# EasyEDA.net
KiCad netlist of a schematic drawn in EasyEDA Pro
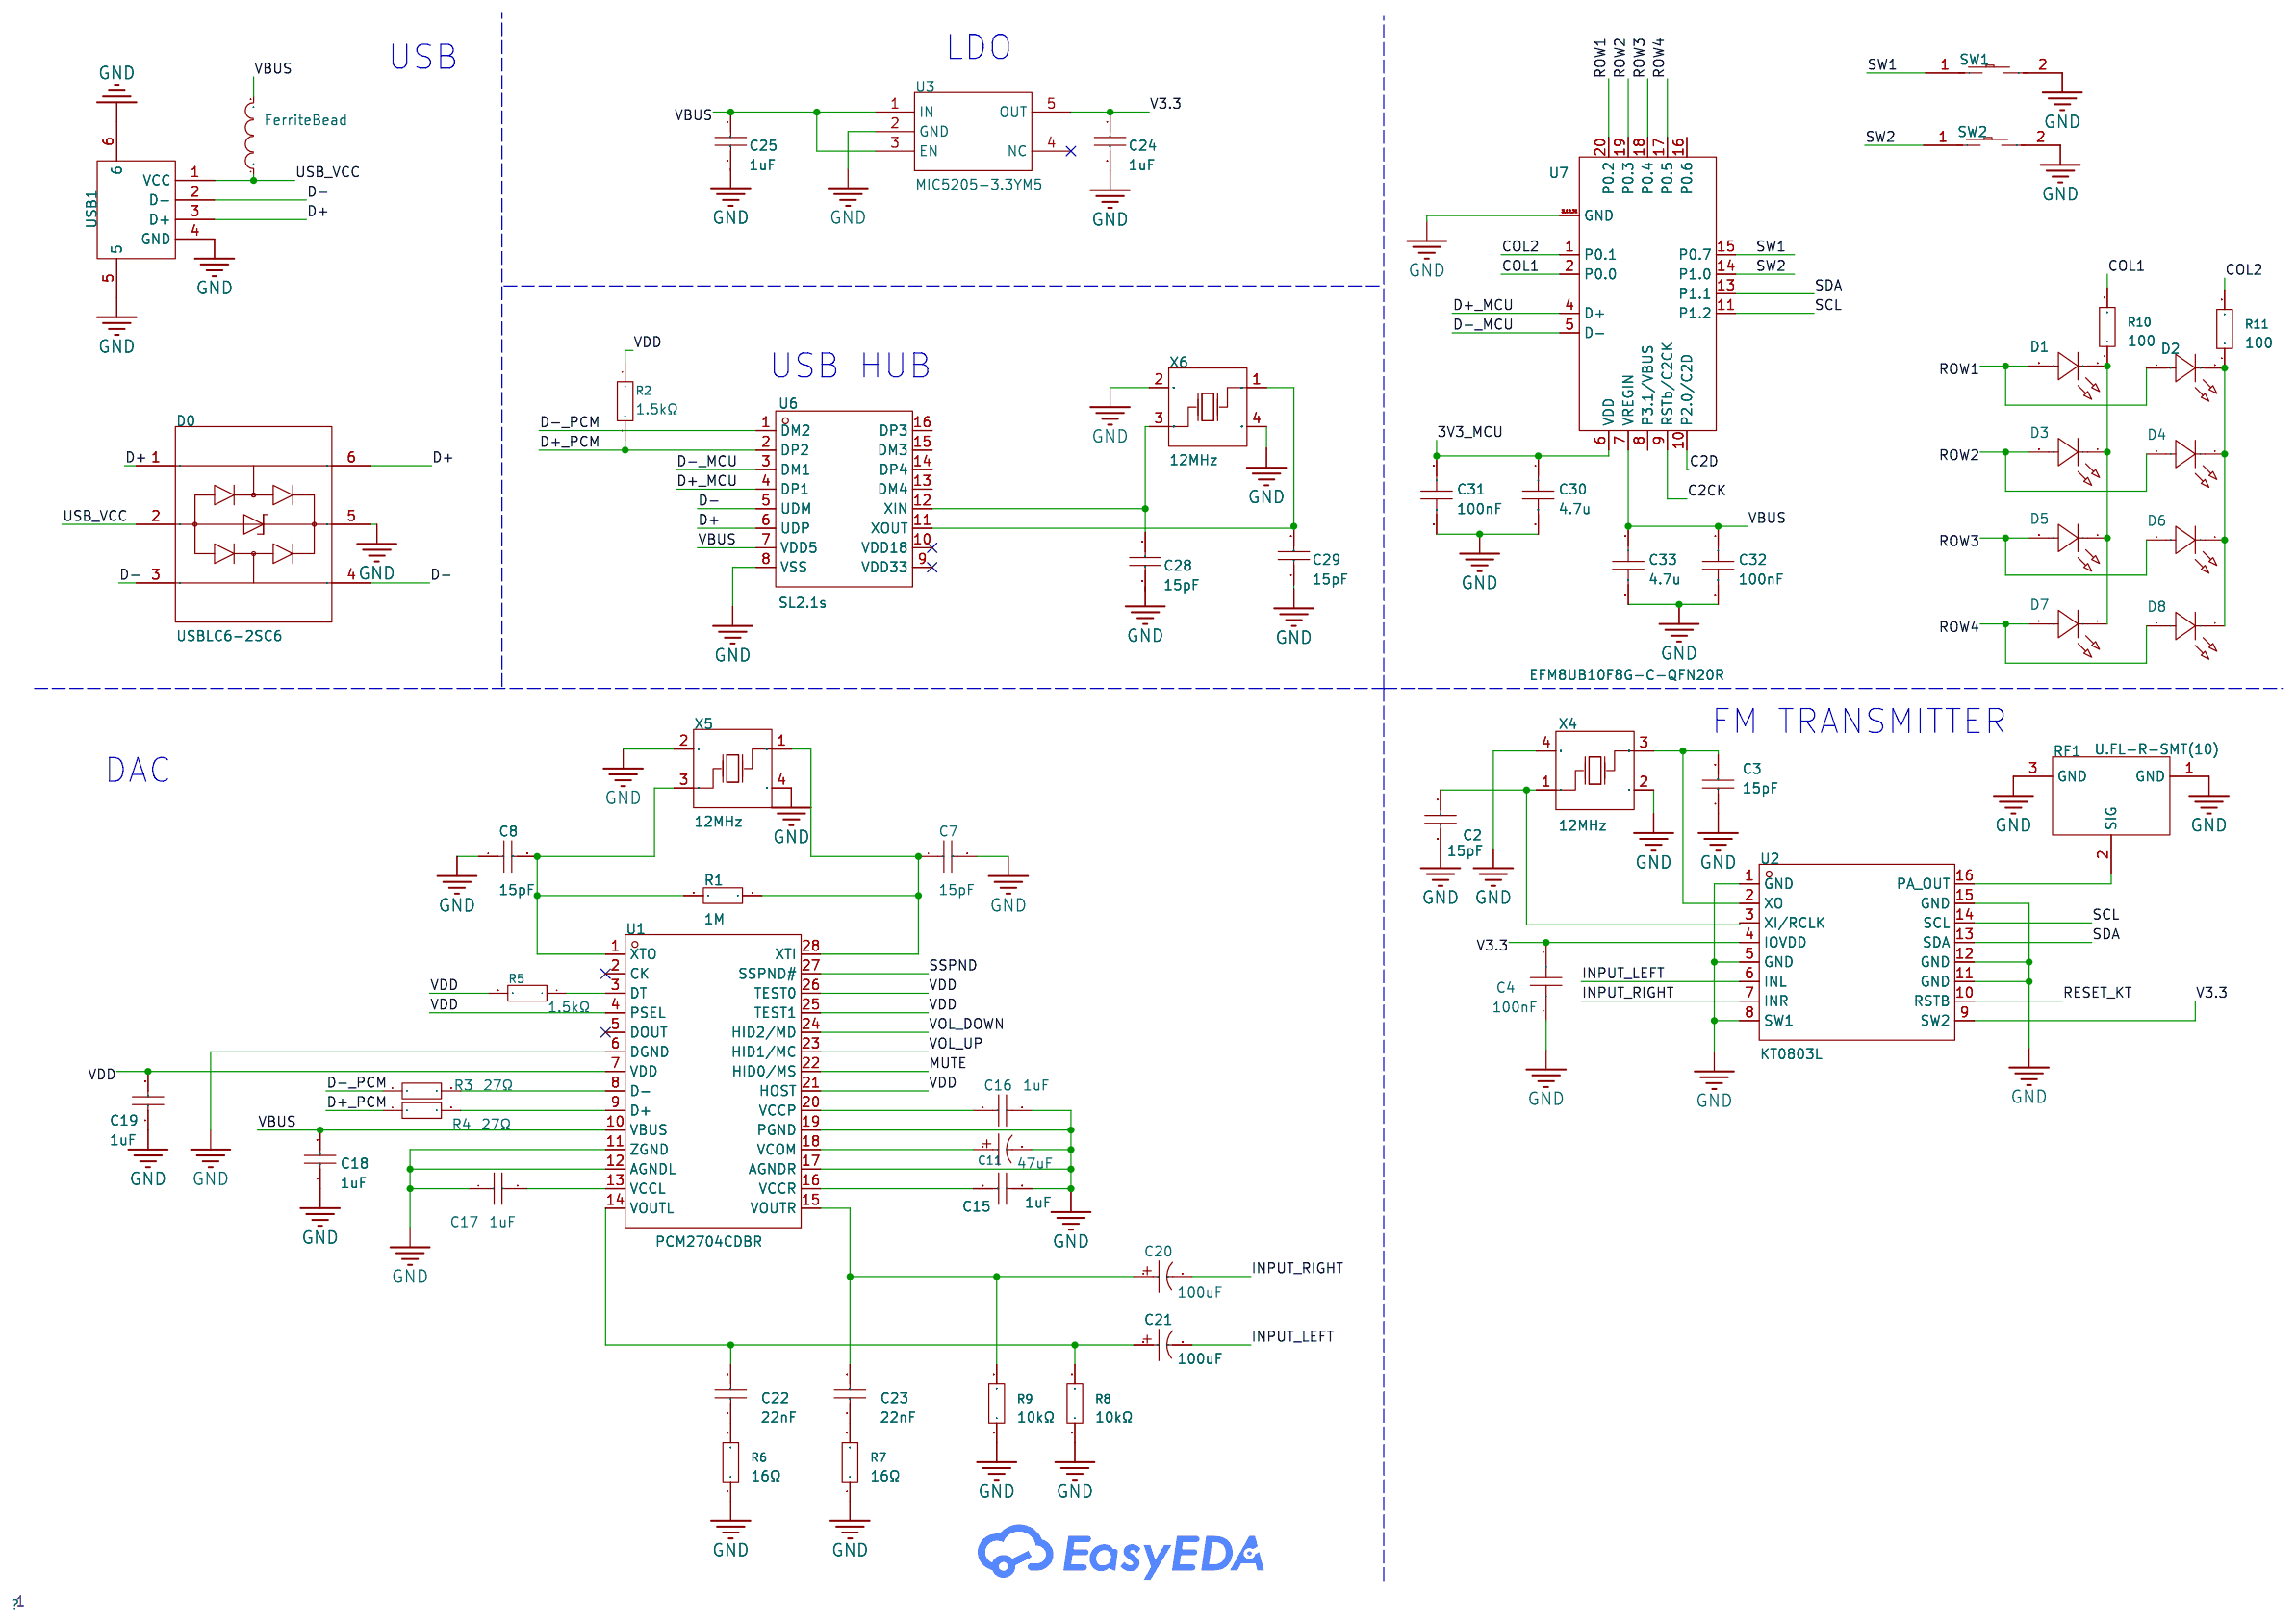
[diagram p0: schematic sheet]

(export (version "E")
  (design (tool "Eeschema 10.0.6"))
  (components
    (comp (ref "C2")
      (value "15pF")
      (footprint "easyedapro:C0402")
      (fields (field (name "Manufacturer Part") "0402CG150J500NT") (field (name "Manufacturer") "FH(风华)"))
      (libsource (lib "easyedapro") (part "0402CG150J500NT"))
    )
    (comp (ref "C3")
      (value "15pF")
      (footprint "easyedapro:C0402")
      (fields (field (name "Manufacturer Part") "0402CG150J500NT") (field (name "Manufacturer") "FH(风华)"))
      (libsource (lib "easyedapro") (part "0402CG150J500NT"))
    )
    (comp (ref "C4")
      (value "100nF")
      (footprint "easyedapro:C0402")
      (fields
        (field (name "Manufacturer Part") "CL05B104KO5NNNC")
        (field (name "Manufacturer") "SAMSUNG(三星)")
      )
      (libsource (lib "easyedapro") (part "CL05B104KO5NNNC"))
    )
    (comp (ref "C7")
      (value "15pF")
      (footprint "easyedapro:C0402")
      (fields (field (name "Manufacturer Part") "0402CG150J500NT") (field (name "Manufacturer") "FH(风华)"))
      (libsource (lib "easyedapro") (part "0402CG150J500NT"))
    )
    (comp (ref "C8")
      (value "15pF")
      (footprint "easyedapro:C0402")
      (fields (field (name "Manufacturer Part") "0402CG150J500NT") (field (name "Manufacturer") "FH(风华)"))
      (libsource (lib "easyedapro") (part "0402CG150J500NT"))
    )
    (comp (ref "C11")
      (value "47uF")
      (footprint "easyedapro:CAP-SMD_BD5.0-L5.3-W5.3-FD")
      (fields (field (name "Manufacturer Part") "RVT1C470M0505") (field (name "Manufacturer") "HONOR(荣誉)"))
      (libsource (lib "easyedapro") (part "RVT1C470M0505"))
    )
    (comp (ref "C15")
      (value "1uF")
      (footprint "easyedapro:C0603")
      (fields
        (field (name "Manufacturer Part") "CL10A105KO8NNNC")
        (field (name "Manufacturer") "SAMSUNG(三星)")
      )
      (libsource (lib "easyedapro") (part "CL10A105KO8NNNC"))
    )
    (comp (ref "C16")
      (value "1uF")
      (footprint "easyedapro:C0603")
      (fields
        (field (name "Manufacturer Part") "CL10A105KO8NNNC")
        (field (name "Manufacturer") "SAMSUNG(三星)")
      )
      (libsource (lib "easyedapro") (part "CL10A105KO8NNNC"))
    )
    (comp (ref "C17")
      (value "1uF")
      (footprint "easyedapro:C0603")
      (fields
        (field (name "Manufacturer Part") "CL10A105KO8NNNC")
        (field (name "Manufacturer") "SAMSUNG(三星)")
      )
      (libsource (lib "easyedapro") (part "CL10A105KO8NNNC"))
    )
    (comp (ref "C18")
      (value "1uF")
      (footprint "easyedapro:C0603")
      (fields
        (field (name "Manufacturer Part") "CL10A105KO8NNNC")
        (field (name "Manufacturer") "SAMSUNG(三星)")
      )
      (libsource (lib "easyedapro") (part "CL10A105KO8NNNC"))
    )
    (comp (ref "C19")
      (value "1uF")
      (footprint "easyedapro:C0603")
      (fields
        (field (name "Manufacturer Part") "CL10A105KO8NNNC")
        (field (name "Manufacturer") "SAMSUNG(三星)")
      )
      (libsource (lib "easyedapro") (part "CL10A105KO8NNNC"))
    )
    (comp (ref "C20")
      (value "100uF")
      (footprint "easyedapro:CAP-SMD_BD6.3-L6.6-W6.6-LS7.2-R-RD")
      (fields (field (name "Manufacturer Part") "RVT1E101M0607") (field (name "Manufacturer") "HONOR(荣誉)"))
      (libsource (lib "easyedapro") (part "RVT1E101M0607"))
    )
    (comp (ref "C21")
      (value "100uF")
      (footprint "easyedapro:CAP-SMD_BD6.3-L6.6-W6.6-LS7.2-R-RD")
      (fields (field (name "Manufacturer Part") "RVT1E101M0607") (field (name "Manufacturer") "HONOR(荣誉)"))
      (libsource (lib "easyedapro") (part "RVT1E101M0607"))
    )
    (comp (ref "C22")
      (value "22nF")
      (footprint "easyedapro:C0402")
      (description "Capacitance:22nF Tolerance:±10% Tolerance:±10% Voltage Rating:50V Temperature Coefficient:X7R")
      (fields (field (name "Manufacturer Part") "0402B223K500NT") (field (name "Manufacturer") "FH(风华)"))
      (libsource (lib "easyedapro") (part "0402B223K500NT"))
    )
    (comp (ref "C23")
      (value "22nF")
      (footprint "easyedapro:C0402")
      (description "Capacitance:22nF Tolerance:±10% Tolerance:±10% Voltage Rating:50V Temperature Coefficient:X7R")
      (fields (field (name "Manufacturer Part") "0402B223K500NT") (field (name "Manufacturer") "FH(风华)"))
      (libsource (lib "easyedapro") (part "0402B223K500NT"))
    )
    (comp (ref "C24")
      (value "1uF")
      (footprint "easyedapro:C0603")
      (fields
        (field (name "Manufacturer Part") "CL10A105KO8NNNC")
        (field (name "Manufacturer") "SAMSUNG(三星)")
      )
      (libsource (lib "easyedapro") (part "CL10A105KO8NNNC"))
    )
    (comp (ref "C25")
      (value "1uF")
      (footprint "easyedapro:C0603")
      (fields
        (field (name "Manufacturer Part") "CL10A105KO8NNNC")
        (field (name "Manufacturer") "SAMSUNG(三星)")
      )
      (libsource (lib "easyedapro") (part "CL10A105KO8NNNC"))
    )
    (comp (ref "C28")
      (value "15pF")
      (footprint "easyedapro:C0402")
      (fields (field (name "Manufacturer Part") "0402CG150J500NT") (field (name "Manufacturer") "FH(风华)"))
      (libsource (lib "easyedapro") (part "0402CG150J500NT"))
    )
    (comp (ref "C29")
      (value "15pF")
      (footprint "easyedapro:C0402")
      (fields (field (name "Manufacturer Part") "0402CG150J500NT") (field (name "Manufacturer") "FH(风华)"))
      (libsource (lib "easyedapro") (part "0402CG150J500NT"))
    )
    (comp (ref "C30")
      (value "4.7u")
      (footprint "easyedapro:C0402")
      (libsource (lib "easyedapro") (part "CAP"))
    )
    (comp (ref "C31")
      (value "100nF")
      (footprint "easyedapro:C0402")
      (libsource (lib "easyedapro") (part "CAP"))
    )
    (comp (ref "C32")
      (value "100nF")
      (footprint "easyedapro:C0402")
      (libsource (lib "easyedapro") (part "CAP"))
    )
    (comp (ref "C33")
      (value "4.7u")
      (footprint "easyedapro:C0402")
      (libsource (lib "easyedapro") (part "CAP"))
    )
    (comp (ref "D0")
      (value "USBLC6-2SC6")
      (footprint "easyedapro:SOT-23-6_L2.9-W1.6-P0.95-LS2.8-BL")
      (libsource (lib "easyedapro") (part "USBLC6-2SC6_C323793"))
    )
    (comp (ref "D1")
      (value "XL-1005UGC")
      (footprint "easyedapro:LED0402-RD_GREEN")
      (fields (field (name "Manufacturer") "XINGLIGHT(成兴光)"))
      (libsource (lib "easyedapro") (part "XL-1005UGC"))
    )
    (comp (ref "D2")
      (value "XL-1005UGC")
      (footprint "easyedapro:LED0402-RD_GREEN")
      (fields (field (name "Manufacturer") "XINGLIGHT(成兴光)"))
      (libsource (lib "easyedapro") (part "XL-1005UGC"))
    )
    (comp (ref "D3")
      (value "XL-1005UGC")
      (footprint "easyedapro:LED0402-RD_GREEN")
      (fields (field (name "Manufacturer") "XINGLIGHT(成兴光)"))
      (libsource (lib "easyedapro") (part "XL-1005UGC"))
    )
    (comp (ref "D4")
      (value "XL-1005UGC")
      (footprint "easyedapro:LED0402-RD_GREEN")
      (fields (field (name "Manufacturer") "XINGLIGHT(成兴光)"))
      (libsource (lib "easyedapro") (part "XL-1005UGC"))
    )
    (comp (ref "D5")
      (value "XL-1005UGC")
      (footprint "easyedapro:LED0402-RD_GREEN")
      (fields (field (name "Manufacturer") "XINGLIGHT(成兴光)"))
      (libsource (lib "easyedapro") (part "XL-1005UGC"))
    )
    (comp (ref "D6")
      (value "XL-1005UGC")
      (footprint "easyedapro:LED0402-RD_GREEN")
      (fields (field (name "Manufacturer") "XINGLIGHT(成兴光)"))
      (libsource (lib "easyedapro") (part "XL-1005UGC"))
    )
    (comp (ref "D7")
      (value "XL-1005UGC")
      (footprint "easyedapro:LED0402-RD_GREEN")
      (fields (field (name "Manufacturer") "XINGLIGHT(成兴光)"))
      (libsource (lib "easyedapro") (part "XL-1005UGC"))
    )
    (comp (ref "D8")
      (value "XL-1005UGC")
      (footprint "easyedapro:LED0402-RD_GREEN")
      (fields (field (name "Manufacturer") "XINGLIGHT(成兴光)"))
      (libsource (lib "easyedapro") (part "XL-1005UGC"))
    )
    (comp (ref "FerriteBead")
      (value "MPZ1608S101ATAH0")
      (footprint "easyedapro:L0603")
      (fields (field (name "Manufacturer") "TDK"))
      (libsource (lib "easyedapro") (part "MPZ1608S101ATAH0"))
    )
    (comp (ref "R1")
      (value "1M")
      (footprint "easyedapro:R0402")
      (fields (field (name "Manufacturer Part") "0402WGF1004TCE") (field (name "Manufacturer") "UniOhm"))
      (libsource (lib "easyedapro") (part "1M"))
    )
    (comp (ref "R2")
      (value "1.5kΩ")
      (footprint "easyedapro:R0402")
      (fields
        (field (name "Manufacturer Part") "0402WGF1501TCE")
        (field (name "Manufacturer") "UNI-ROYAL(厚声)")
      )
      (libsource (lib "easyedapro") (part "0402WGF1501TCE"))
    )
    (comp (ref "R3")
      (value "27Ω")
      (footprint "easyedapro:R0402")
      (fields
        (field (name "Manufacturer Part") "0402WGF270JTCE")
        (field (name "Manufacturer") "UNI-ROYAL(厚声)")
      )
      (libsource (lib "easyedapro") (part "0402WGF270JTCE"))
    )
    (comp (ref "R4")
      (value "27Ω")
      (footprint "easyedapro:R0402")
      (fields
        (field (name "Manufacturer Part") "0402WGF270JTCE")
        (field (name "Manufacturer") "UNI-ROYAL(厚声)")
      )
      (libsource (lib "easyedapro") (part "0402WGF270JTCE"))
    )
    (comp (ref "R5")
      (value "1.5kΩ")
      (footprint "easyedapro:R0402")
      (fields
        (field (name "Manufacturer Part") "0402WGF1501TCE")
        (field (name "Manufacturer") "UNI-ROYAL(厚声)")
      )
      (libsource (lib "easyedapro") (part "0402WGF1501TCE"))
    )
    (comp (ref "R6")
      (value "16Ω")
      (footprint "easyedapro:R0603")
      (fields
        (field (name "Manufacturer Part") "0603WAF160JT5E")
        (field (name "Manufacturer") "UNI-ROYAL(厚声)")
      )
      (libsource (lib "easyedapro") (part "0603WAF160JT5E"))
    )
    (comp (ref "R7")
      (value "16Ω")
      (footprint "easyedapro:R0603")
      (fields
        (field (name "Manufacturer Part") "0603WAF160JT5E")
        (field (name "Manufacturer") "UNI-ROYAL(厚声)")
      )
      (libsource (lib "easyedapro") (part "0603WAF160JT5E"))
    )
    (comp (ref "R8")
      (value "10kΩ")
      (footprint "easyedapro:R0402")
      (fields
        (field (name "Manufacturer Part") "0402WGJ0103TCE")
        (field (name "Manufacturer") "UNI-ROYAL(厚声)")
      )
      (libsource (lib "easyedapro") (part "0402WGJ0103TCE"))
    )
    (comp (ref "R9")
      (value "10kΩ")
      (footprint "easyedapro:R0402")
      (fields
        (field (name "Manufacturer Part") "0402WGJ0103TCE")
        (field (name "Manufacturer") "UNI-ROYAL(厚声)")
      )
      (libsource (lib "easyedapro") (part "0402WGJ0103TCE"))
    )
    (comp (ref "R10")
      (value "100")
      (footprint "easyedapro:R0402")
      (fields
        (field (name "Manufacturer Part") "0402WGJ0103TCE")
        (field (name "Manufacturer") "UNI-ROYAL(厚声)")
      )
      (libsource (lib "easyedapro") (part "0402WGJ0103TCE"))
    )
    (comp (ref "R11")
      (value "100")
      (footprint "easyedapro:R0402")
      (fields
        (field (name "Manufacturer Part") "0402WGJ0103TCE")
        (field (name "Manufacturer") "UNI-ROYAL(厚声)")
      )
      (libsource (lib "easyedapro") (part "0402WGJ0103TCE"))
    )
    (comp (ref "RF1")
      (value "U.FL-R-SMT(10)")
      (footprint "easyedapro:ANT-SMD_UFL-R-SMT01")
      (fields (field (name "Manufacturer") "HRS(广濑)"))
      (libsource (lib "easyedapro") (part "U.FL-R-SMT(10)"))
    )
    (comp (ref "SW1")
      (value "B3U-1000P")
      (footprint "easyedapro:KEY-SMD_B3U-1000PM")
      (fields (field (name "Manufacturer") "OMRON(欧姆龙)"))
      (libsource (lib "easyedapro") (part "B3U-1000P"))
    )
    (comp (ref "SW2")
      (value "B3U-1000P")
      (footprint "easyedapro:KEY-SMD_B3U-1000PM")
      (fields (field (name "Manufacturer") "OMRON(欧姆龙)"))
      (libsource (lib "easyedapro") (part "B3U-1000P"))
    )
    (comp (ref "U1")
      (value "PCM2704CDBR")
      (footprint "easyedapro:SSOP-28_L10.2-W5.3-P0.65-LS7.8-BL")
      (fields (field (name "Manufacturer") "TI(德州仪器)"))
      (libsource (lib "easyedapro") (part "PCM2704CDBR"))
    )
    (comp (ref "U2")
      (value "KT0803L")
      (footprint "easyedapro:SOP-16_L9.9-W3.9-P1.27-LS6.0-BL")
      (libsource (lib "easyedapro") (part "KT0803L"))
    )
    (comp (ref "U3")
      (value "MIC5205-3.3YM5")
      (fields (field (name "Manufacturer") "TECH PUBLIC(台舟)"))
      (libsource (lib "easyedapro") (part "TLV73333PDBVR"))
    )
    (comp (ref "U6")
      (value "SL2.1s")
      (footprint "easyedapro:SSOP-16_L4.6-W2.6-P0.53-LS4.0-BL")
      (fields (field (name "Manufacturer") "CoreChips(和芯润德)"))
      (libsource (lib "easyedapro") (part "SL2.1S"))
    )
    (comp (ref "U7")
      (value "EFM8UB10F8G-C-QFN20R")
      (footprint "easyedapro:QFN-20_L3.0-W3.0-P0.50-TL-EP1.7_SILICON_C8051F85X")
      (fields (field (name "Manufacturer") "SKYWORKS/SILICON LABS(芯科)"))
      (libsource (lib "easyedapro") (part "EFM8UB10F8G-C-QFN20R"))
    )
    (comp (ref "USB1")
      (value "U-G-O4DD-W-1")
      (footprint "easyedapro:USB-A-TH_U-G-04WD-W-01")
      (fields (field (name "Manufacturer") "韩国韩荣"))
      (libsource (lib "easyedapro") (part "U-G-04DD-W-01"))
    )
    (comp (ref "X4")
      (value "12MHz")
      (fields
        (field (name "Manufacturer Part") "SX2B12.000F1010F30")
        (field (name "Manufacturer") "SCTF(星通时频)")
      )
      (libsource (lib "easyedapro") (part "X322512MSB4SI"))
    )
    (comp (ref "X5")
      (value "12MHz")
      (fields
        (field (name "Manufacturer Part") "SX2B12.000F1010F30")
        (field (name "Manufacturer") "SCTF(星通时频)")
      )
      (libsource (lib "easyedapro") (part "X322512MSB4SI"))
    )
    (comp (ref "X6")
      (value "12MHz")
      (fields
        (field (name "Manufacturer Part") "SX2B12.000F1010F30")
        (field (name "Manufacturer") "SCTF(星通时频)")
      )
      (libsource (lib "easyedapro") (part "X322512MSB4SI"))
    )
  )
  (nets
    (net (code "1") (name "/3V3_MCU") (class "Default")
      (node (ref "C30") (pin "1") (pinfunction "1_1") (pintype "input"))
      (node (ref "C31") (pin "1") (pinfunction "1_1") (pintype "input"))
      (node (ref "U7") (pin "6") (pinfunction "VDD_6") (pintype "unspecified"))
    )
    (net (code "2") (name "/C2CK") (class "Default")
      (node (ref "U7") (pin "9") (pinfunction "RSTb/C2CK_9") (pintype "unspecified"))
    )
    (net (code "3") (name "/C2D") (class "Default")
      (node (ref "U7") (pin "10") (pinfunction "P2.0/C2D_10") (pintype "unspecified"))
    )
    (net (code "4") (name "/COL1") (class "Default")
      (node (ref "R10") (pin "2") (pinfunction "2_2") (pintype "input"))
      (node (ref "U7") (pin "2") (pinfunction "P0.0_2") (pintype "unspecified"))
    )
    (net (code "5") (name "/COL2") (class "Default")
      (node (ref "R11") (pin "2") (pinfunction "2_2") (pintype "input"))
      (node (ref "U7") (pin "1") (pinfunction "P0.1_1") (pintype "unspecified"))
    )
    (net (code "6") (name "/D+") (class "Default")
      (node (ref "D0") (pin "1") (pinfunction "1_1") (pintype "input"))
      (node (ref "D0") (pin "6") (pinfunction "6_6") (pintype "input"))
      (node (ref "U6") (pin "6") (pinfunction "UDP_6") (pintype "unspecified"))
      (node (ref "USB1") (pin "3") (pinfunction "D+_3") (pintype "unspecified"))
    )
    (net (code "7") (name "/D+_MCU") (class "Default")
      (node (ref "U6") (pin "4") (pinfunction "DP1_4") (pintype "unspecified"))
      (node (ref "U7") (pin "4") (pinfunction "D+_4") (pintype "unspecified"))
    )
    (net (code "8") (name "/D+_PCM") (class "Default")
      (node (ref "R2") (pin "2") (pinfunction "2_2") (pintype "input"))
      (node (ref "R4") (pin "1") (pinfunction "1_1") (pintype "input"))
      (node (ref "U6") (pin "2") (pinfunction "DP2_2") (pintype "unspecified"))
    )
    (net (code "9") (name "/D-") (class "Default")
      (node (ref "D0") (pin "3") (pinfunction "3_3") (pintype "input"))
      (node (ref "D0") (pin "4") (pinfunction "4_4") (pintype "input"))
      (node (ref "U6") (pin "5") (pinfunction "UDM_5") (pintype "unspecified"))
      (node (ref "USB1") (pin "2") (pinfunction "D-_2") (pintype "unspecified"))
    )
    (net (code "10") (name "/D-_MCU") (class "Default")
      (node (ref "U6") (pin "3") (pinfunction "DM1_3") (pintype "unspecified"))
      (node (ref "U7") (pin "5") (pinfunction "D-_5") (pintype "unspecified"))
    )
    (net (code "11") (name "/D-_PCM") (class "Default")
      (node (ref "R3") (pin "1") (pinfunction "1_1") (pintype "input"))
      (node (ref "U6") (pin "1") (pinfunction "DM2_1") (pintype "unspecified"))
    )
    (net (code "12") (name "/INPUT_LEFT") (class "Default")
      (node (ref "C21") (pin "2") (pinfunction "2_2") (pintype "input"))
      (node (ref "U2") (pin "6") (pinfunction "INL_6") (pintype "unspecified"))
    )
    (net (code "13") (name "/INPUT_RIGHT") (class "Default")
      (node (ref "C20") (pin "2") (pinfunction "2_2") (pintype "input"))
      (node (ref "U2") (pin "7") (pinfunction "INR_7") (pintype "unspecified"))
    )
    (net (code "14") (name "/MUTE") (class "Default")
      (node (ref "U1") (pin "22") (pinfunction "HID0/MS_22") (pintype "unspecified"))
    )
    (net (code "15") (name "/RESET_KT") (class "Default")
      (node (ref "U2") (pin "10") (pinfunction "RSTB_10") (pintype "unspecified"))
    )
    (net (code "16") (name "/ROW1") (class "Default")
      (node (ref "D1") (pin "2") (pinfunction "A_2") (pintype "unspecified"))
      (node (ref "D2") (pin "2") (pinfunction "A_2") (pintype "unspecified"))
      (node (ref "U7") (pin "20") (pinfunction "P0.2_20") (pintype "unspecified"))
    )
    (net (code "17") (name "/ROW2") (class "Default")
      (node (ref "D3") (pin "2") (pinfunction "A_2") (pintype "unspecified"))
      (node (ref "D4") (pin "2") (pinfunction "A_2") (pintype "unspecified"))
      (node (ref "U7") (pin "19") (pinfunction "P0.3_19") (pintype "unspecified"))
    )
    (net (code "18") (name "/ROW3") (class "Default")
      (node (ref "D5") (pin "2") (pinfunction "A_2") (pintype "unspecified"))
      (node (ref "D6") (pin "2") (pinfunction "A_2") (pintype "unspecified"))
      (node (ref "U7") (pin "18") (pinfunction "P0.4_18") (pintype "unspecified"))
    )
    (net (code "19") (name "/ROW4") (class "Default")
      (node (ref "D7") (pin "2") (pinfunction "A_2") (pintype "unspecified"))
      (node (ref "D8") (pin "2") (pinfunction "A_2") (pintype "unspecified"))
      (node (ref "U7") (pin "17") (pinfunction "P0.5_17") (pintype "unspecified"))
    )
    (net (code "20") (name "/SCL") (class "Default")
      (node (ref "U2") (pin "14") (pinfunction "SCL_14") (pintype "unspecified"))
      (node (ref "U7") (pin "11") (pinfunction "P1.2_11") (pintype "unspecified"))
    )
    (net (code "21") (name "/SDA") (class "Default")
      (node (ref "U2") (pin "13") (pinfunction "SDA_13") (pintype "unspecified"))
      (node (ref "U7") (pin "13") (pinfunction "P1.1_13") (pintype "unspecified"))
    )
    (net (code "22") (name "/SSPND") (class "Default")
      (node (ref "U1") (pin "27") (pinfunction "SSPND#_27") (pintype "unspecified"))
    )
    (net (code "23") (name "/SW1") (class "Default")
      (node (ref "SW1") (pin "1") (pinfunction "1_1") (pintype "unspecified"))
      (node (ref "U7") (pin "15") (pinfunction "P0.7_15") (pintype "unspecified"))
    )
    (net (code "24") (name "/SW2") (class "Default")
      (node (ref "SW2") (pin "1") (pinfunction "1_1") (pintype "unspecified"))
      (node (ref "U7") (pin "14") (pinfunction "P1.0_14") (pintype "unspecified"))
    )
    (net (code "25") (name "/USB_VCC") (class "Default")
      (node (ref "D0") (pin "2") (pinfunction "2_2") (pintype "input"))
      (node (ref "FerriteBead") (pin "1") (pinfunction "1_1") (pintype "unspecified"))
      (node (ref "USB1") (pin "1") (pinfunction "VCC_1") (pintype "unspecified"))
    )
    (net (code "26") (name "/V3.3") (class "Default")
      (node (ref "C24") (pin "1") (pinfunction "1_1") (pintype "input"))
      (node (ref "C4") (pin "2") (pinfunction "2_2") (pintype "unspecified"))
      (node (ref "U2") (pin "4") (pinfunction "IOVDD_4") (pintype "unspecified"))
      (node (ref "U2") (pin "9") (pinfunction "SW2_9") (pintype "unspecified"))
      (node (ref "U3") (pin "5") (pinfunction "OUT_5") (pintype "unspecified"))
    )
    (net (code "27") (name "/VBUS") (class "Default")
      (node (ref "C18") (pin "2") (pinfunction "2_2") (pintype "input"))
      (node (ref "C25") (pin "1") (pinfunction "1_1") (pintype "input"))
      (node (ref "C32") (pin "1") (pinfunction "1_1") (pintype "input"))
      (node (ref "C33") (pin "1") (pinfunction "1_1") (pintype "input"))
      (node (ref "FerriteBead") (pin "2") (pinfunction "2_2") (pintype "unspecified"))
      (node (ref "U1") (pin "10") (pinfunction "VBUS_10") (pintype "unspecified"))
      (node (ref "U3") (pin "1") (pinfunction "IN_1") (pintype "unspecified"))
      (node (ref "U3") (pin "3") (pinfunction "EN_3") (pintype "unspecified"))
      (node (ref "U6") (pin "7") (pinfunction "VDD5_7") (pintype "unspecified"))
      (node (ref "U7") (pin "7") (pinfunction "VREGIN_7") (pintype "unspecified"))
    )
    (net (code "28") (name "/VDD") (class "Default")
      (node (ref "C19") (pin "2") (pinfunction "2_2") (pintype "input"))
      (node (ref "R2") (pin "1") (pinfunction "1_1") (pintype "input"))
      (node (ref "R5") (pin "2") (pinfunction "2_2") (pintype "input"))
      (node (ref "U1") (pin "21") (pinfunction "HOST_21") (pintype "unspecified"))
      (node (ref "U1") (pin "25") (pinfunction "TEST1_25") (pintype "unspecified"))
      (node (ref "U1") (pin "26") (pinfunction "TEST0_26") (pintype "unspecified"))
      (node (ref "U1") (pin "4") (pinfunction "PSEL_4") (pintype "unspecified"))
      (node (ref "U1") (pin "7") (pinfunction "VDD_7") (pintype "unspecified"))
    )
    (net (code "29") (name "/VOL_DOWN") (class "Default")
      (node (ref "U1") (pin "24") (pinfunction "HID2/MD_24") (pintype "unspecified"))
    )
    (net (code "30") (name "/VOL_UP") (class "Default")
      (node (ref "U1") (pin "23") (pinfunction "HID1/MC_23") (pintype "unspecified"))
    )
    (net (code "31") (name "GND") (class "Default")
      (node (ref "C11") (pin "2") (pinfunction "2_2") (pintype "input"))
      (node (ref "C15") (pin "2") (pinfunction "2_2") (pintype "input"))
      (node (ref "C16") (pin "2") (pinfunction "2_2") (pintype "input"))
      (node (ref "C17") (pin "1") (pinfunction "1_1") (pintype "input"))
      (node (ref "C18") (pin "1") (pinfunction "1_1") (pintype "input"))
      (node (ref "C19") (pin "1") (pinfunction "1_1") (pintype "input"))
      (node (ref "C2") (pin "1") (pinfunction "1_1") (pintype "input"))
      (node (ref "C24") (pin "2") (pinfunction "2_2") (pintype "input"))
      (node (ref "C25") (pin "2") (pinfunction "2_2") (pintype "input"))
      (node (ref "C28") (pin "1") (pinfunction "1_1") (pintype "input"))
      (node (ref "C29") (pin "1") (pinfunction "1_1") (pintype "input"))
      (node (ref "C3") (pin "1") (pinfunction "1_1") (pintype "input"))
      (node (ref "C30") (pin "2") (pinfunction "2_2") (pintype "input"))
      (node (ref "C31") (pin "2") (pinfunction "2_2") (pintype "input"))
      (node (ref "C32") (pin "2") (pinfunction "2_2") (pintype "input"))
      (node (ref "C33") (pin "2") (pinfunction "2_2") (pintype "input"))
      (node (ref "C4") (pin "1") (pinfunction "1_1") (pintype "unspecified"))
      (node (ref "C7") (pin "2") (pinfunction "2_2") (pintype "input"))
      (node (ref "C8") (pin "1") (pinfunction "1_1") (pintype "input"))
      (node (ref "D0") (pin "5") (pinfunction "5_5") (pintype "input"))
      (node (ref "R6") (pin "1") (pinfunction "1_1") (pintype "input"))
      (node (ref "R7") (pin "1") (pinfunction "1_1") (pintype "input"))
      (node (ref "R8") (pin "1") (pinfunction "1_1") (pintype "input"))
      (node (ref "R9") (pin "1") (pinfunction "1_1") (pintype "input"))
      (node (ref "RF1") (pin "1") (pinfunction "GND_1") (pintype "unspecified"))
      (node (ref "RF1") (pin "3") (pinfunction "GND_3") (pintype "unspecified"))
      (node (ref "SW1") (pin "2") (pinfunction "2_2") (pintype "unspecified"))
      (node (ref "SW2") (pin "2") (pinfunction "2_2") (pintype "unspecified"))
      (node (ref "U1") (pin "11") (pinfunction "ZGND_11") (pintype "unspecified"))
      (node (ref "U1") (pin "12") (pinfunction "AGNDL_12") (pintype "unspecified"))
      (node (ref "U1") (pin "17") (pinfunction "AGNDR_17") (pintype "unspecified"))
      (node (ref "U1") (pin "19") (pinfunction "PGND_19") (pintype "unspecified"))
      (node (ref "U1") (pin "6") (pinfunction "DGND_6") (pintype "unspecified"))
      (node (ref "U2") (pin "1") (pinfunction "GND_1") (pintype "unspecified"))
      (node (ref "U2") (pin "11") (pinfunction "GND_11") (pintype "unspecified"))
      (node (ref "U2") (pin "12") (pinfunction "GND_12") (pintype "unspecified"))
      (node (ref "U2") (pin "15") (pinfunction "GND_15") (pintype "unspecified"))
      (node (ref "U2") (pin "5") (pinfunction "GND_5") (pintype "unspecified"))
      (node (ref "U2") (pin "8") (pinfunction "SW1_8") (pintype "unspecified"))
      (node (ref "U3") (pin "2") (pinfunction "GND_2") (pintype "unspecified"))
      (node (ref "U6") (pin "8") (pinfunction "VSS_8") (pintype "unspecified"))
      (node (ref "U7") (pin "3,12,21") (pinfunction "GND_3,12,21") (pintype "unspecified"))
      (node (ref "USB1") (pin "4") (pinfunction "GND_4") (pintype "unspecified"))
      (node (ref "USB1") (pin "5") (pinfunction "5_5") (pintype "unspecified"))
      (node (ref "USB1") (pin "6") (pinfunction "6_6") (pintype "unspecified"))
      (node (ref "X4") (pin "2") (pinfunction "GND_2") (pintype "unspecified"))
      (node (ref "X4") (pin "4") (pinfunction "GND_4") (pintype "unspecified"))
      (node (ref "X5") (pin "2") (pinfunction "GND_2") (pintype "unspecified"))
      (node (ref "X5") (pin "4") (pinfunction "GND_4") (pintype "unspecified"))
      (node (ref "X6") (pin "2") (pinfunction "GND_2") (pintype "unspecified"))
      (node (ref "X6") (pin "4") (pinfunction "GND_4") (pintype "unspecified"))
    )
    (net (code "32") (name "Net-(C22-Pad1)") (class "Default")
      (node (ref "C22") (pin "1") (pinfunction "1_1") (pintype "input"))
      (node (ref "R6") (pin "2") (pinfunction "2_2") (pintype "input"))
    )
    (net (code "33") (name "Net-(C23-Pad1)") (class "Default")
      (node (ref "C23") (pin "1") (pinfunction "1_1") (pintype "input"))
      (node (ref "R7") (pin "2") (pinfunction "2_2") (pintype "input"))
    )
    (net (code "34") (name "Net-(D1-K)") (class "Default")
      (node (ref "D1") (pin "1") (pinfunction "K_1") (pintype "unspecified"))
      (node (ref "D3") (pin "1") (pinfunction "K_1") (pintype "unspecified"))
      (node (ref "D5") (pin "1") (pinfunction "K_1") (pintype "unspecified"))
      (node (ref "D7") (pin "1") (pinfunction "K_1") (pintype "unspecified"))
      (node (ref "R10") (pin "1") (pinfunction "1_1") (pintype "input"))
    )
    (net (code "35") (name "Net-(D2-K)") (class "Default")
      (node (ref "D2") (pin "1") (pinfunction "K_1") (pintype "unspecified"))
      (node (ref "D4") (pin "1") (pinfunction "K_1") (pintype "unspecified"))
      (node (ref "D6") (pin "1") (pinfunction "K_1") (pintype "unspecified"))
      (node (ref "D8") (pin "1") (pinfunction "K_1") (pintype "unspecified"))
      (node (ref "R11") (pin "1") (pinfunction "1_1") (pintype "input"))
    )
    (net (code "36") (name "Net-(RF1-SIG)") (class "Default")
      (node (ref "RF1") (pin "2") (pinfunction "SIG_2") (pintype "unspecified"))
      (node (ref "U2") (pin "16") (pinfunction "PA_OUT_16") (pintype "unspecified"))
    )
    (net (code "37") (name "Net-(U1-D+)") (class "Default")
      (node (ref "R4") (pin "2") (pinfunction "2_2") (pintype "input"))
      (node (ref "U1") (pin "9") (pinfunction "D+_9") (pintype "unspecified"))
    )
    (net (code "38") (name "Net-(U1-D-)") (class "Default")
      (node (ref "R3") (pin "2") (pinfunction "2_2") (pintype "input"))
      (node (ref "U1") (pin "8") (pinfunction "D-_8") (pintype "unspecified"))
    )
    (net (code "39") (name "Net-(U1-DT)") (class "Default")
      (node (ref "R5") (pin "1") (pinfunction "1_1") (pintype "input"))
      (node (ref "U1") (pin "3") (pinfunction "DT_3") (pintype "unspecified"))
    )
    (net (code "40") (name "Net-(U1-VCCL)") (class "Default")
      (node (ref "C17") (pin "2") (pinfunction "2_2") (pintype "input"))
      (node (ref "U1") (pin "13") (pinfunction "VCCL_13") (pintype "unspecified"))
    )
    (net (code "41") (name "Net-(U1-VCCP)") (class "Default")
      (node (ref "C16") (pin "1") (pinfunction "1_1") (pintype "input"))
      (node (ref "U1") (pin "20") (pinfunction "VCCP_20") (pintype "unspecified"))
    )
    (net (code "42") (name "Net-(U1-VCCR)") (class "Default")
      (node (ref "C15") (pin "1") (pinfunction "1_1") (pintype "input"))
      (node (ref "U1") (pin "16") (pinfunction "VCCR_16") (pintype "unspecified"))
    )
    (net (code "43") (name "Net-(U1-VCOM)") (class "Default")
      (node (ref "C11") (pin "1") (pinfunction "1_1") (pintype "input"))
      (node (ref "U1") (pin "18") (pinfunction "VCOM_18") (pintype "unspecified"))
    )
    (net (code "44") (name "Net-(U1-VOUTL)") (class "Default")
      (node (ref "C21") (pin "1") (pinfunction "1_1") (pintype "input"))
      (node (ref "C22") (pin "2") (pinfunction "2_2") (pintype "input"))
      (node (ref "R8") (pin "2") (pinfunction "2_2") (pintype "input"))
      (node (ref "U1") (pin "14") (pinfunction "VOUTL_14") (pintype "unspecified"))
    )
    (net (code "45") (name "Net-(U1-VOUTR)") (class "Default")
      (node (ref "C20") (pin "1") (pinfunction "1_1") (pintype "input"))
      (node (ref "C23") (pin "2") (pinfunction "2_2") (pintype "input"))
      (node (ref "R9") (pin "2") (pinfunction "2_2") (pintype "input"))
      (node (ref "U1") (pin "15") (pinfunction "VOUTR_15") (pintype "unspecified"))
    )
    (net (code "46") (name "Net-(U1-XTI)") (class "Default")
      (node (ref "C7") (pin "1") (pinfunction "1_1") (pintype "input"))
      (node (ref "R1") (pin "2") (pinfunction "2_2") (pintype "input"))
      (node (ref "U1") (pin "28") (pinfunction "XTI_28") (pintype "unspecified"))
      (node (ref "X5") (pin "1") (pinfunction "OSC1_1") (pintype "unspecified"))
    )
    (net (code "47") (name "Net-(U1-XTO)") (class "Default")
      (node (ref "C8") (pin "2") (pinfunction "2_2") (pintype "input"))
      (node (ref "R1") (pin "1") (pinfunction "1_1") (pintype "input"))
      (node (ref "U1") (pin "1") (pinfunction "XTO_1") (pintype "unspecified"))
      (node (ref "X5") (pin "3") (pinfunction "OSC2_3") (pintype "unspecified"))
    )
    (net (code "48") (name "Net-(U2-XI{slash}RCLK)") (class "Default")
      (node (ref "C2") (pin "2") (pinfunction "2_2") (pintype "input"))
      (node (ref "U2") (pin "3") (pinfunction "XI/RCLK_3") (pintype "unspecified"))
      (node (ref "X4") (pin "1") (pinfunction "OSC1_1") (pintype "unspecified"))
    )
    (net (code "49") (name "Net-(U2-XO)") (class "Default")
      (node (ref "C3") (pin "2") (pinfunction "2_2") (pintype "input"))
      (node (ref "U2") (pin "2") (pinfunction "XO_2") (pintype "unspecified"))
      (node (ref "X4") (pin "3") (pinfunction "OSC2_3") (pintype "unspecified"))
    )
    (net (code "50") (name "Net-(U6-XIN)") (class "Default")
      (node (ref "C28") (pin "2") (pinfunction "2_2") (pintype "input"))
      (node (ref "U6") (pin "12") (pinfunction "XIN_12") (pintype "unspecified"))
      (node (ref "X6") (pin "3") (pinfunction "OSC2_3") (pintype "unspecified"))
    )
    (net (code "51") (name "Net-(U6-XOUT)") (class "Default")
      (node (ref "C29") (pin "2") (pinfunction "2_2") (pintype "input"))
      (node (ref "U6") (pin "11") (pinfunction "XOUT_11") (pintype "unspecified"))
      (node (ref "X6") (pin "1") (pinfunction "OSC1_1") (pintype "unspecified"))
    )
    (net (code "52") (name "unconnected-(U1-CK-Pad2)") (class "Default")
      (node (ref "U1") (pin "2") (pinfunction "CK_2") (pintype "unspecified+no_connect"))
    )
    (net (code "53") (name "unconnected-(U1-DOUT-Pad5)") (class "Default")
      (node (ref "U1") (pin "5") (pinfunction "DOUT_5") (pintype "unspecified+no_connect"))
    )
    (net (code "54") (name "unconnected-(U3-NC-Pad4)") (class "Default")
      (node (ref "U3") (pin "4") (pinfunction "NC_4") (pintype "unspecified+no_connect"))
    )
    (net (code "55") (name "unconnected-(U6-DM3-Pad15)") (class "Default")
      (node (ref "U6") (pin "15") (pinfunction "DM3_15") (pintype "unspecified"))
    )
    (net (code "56") (name "unconnected-(U6-DM4-Pad13)") (class "Default")
      (node (ref "U6") (pin "13") (pinfunction "DM4_13") (pintype "unspecified"))
    )
    (net (code "57") (name "unconnected-(U6-DP3-Pad16)") (class "Default")
      (node (ref "U6") (pin "16") (pinfunction "DP3_16") (pintype "unspecified"))
    )
    (net (code "58") (name "unconnected-(U6-DP4-Pad14)") (class "Default")
      (node (ref "U6") (pin "14") (pinfunction "DP4_14") (pintype "unspecified"))
    )
    (net (code "59") (name "unconnected-(U6-VDD18-Pad10)") (class "Default")
      (node (ref "U6") (pin "10") (pinfunction "VDD18_10") (pintype "unspecified+no_connect"))
    )
    (net (code "60") (name "unconnected-(U6-VDD33-Pad9)") (class "Default")
      (node (ref "U6") (pin "9") (pinfunction "VDD33_9") (pintype "unspecified+no_connect"))
    )
    (net (code "61") (name "unconnected-(U7-P0.6-Pad16)") (class "Default")
      (node (ref "U7") (pin "16") (pinfunction "P0.6_16") (pintype "unspecified"))
    )
    (net (code "62") (name "unconnected-(U7-P3.1{slash}VBUS-Pad8)") (class "Default")
      (node (ref "U7") (pin "8") (pinfunction "P3.1/VBUS_8") (pintype "unspecified"))
    )
  )
)
